# power_stage.net
KiCad netlist of a schematic drawn in Altium Designer
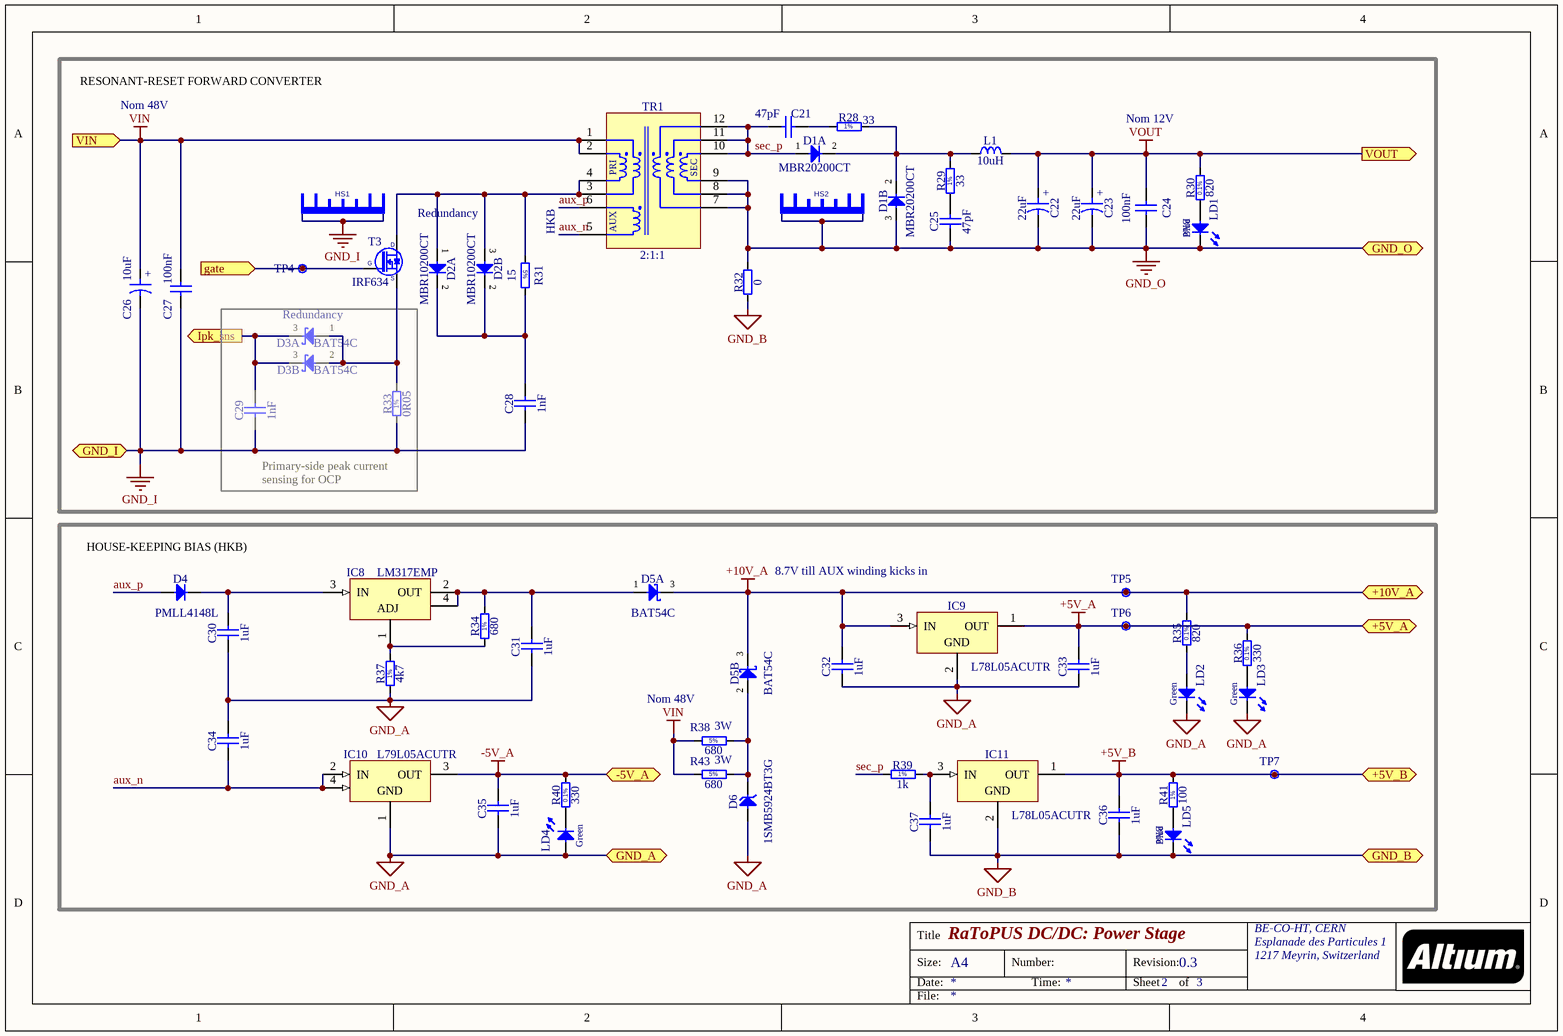
[diagram p0: power_stage.schdoc]

(export (version "E")
  (design (tool "Eeschema 10.0.6"))
  (components
    (comp (ref "C21")
      (value "47pF")
      (footprint "CAPC2012X88N")
      (description "Non-polarised capacitor")
      (fields
        (field (name "PART NUMBER") "CC0805_47PF_50V_5%_C0G_KEMET_C0805C470J5GACAUTO")
        (field (name "VOLTAGE") "50V")
        (field (name "AUTHOR") "CERN DEM JLC")
      )
      (libsource (lib "Capacitors") (part "Capacitor - non polarized"))
    )
    (comp (ref "C22")
      (value "22uF")
      (footprint "CAPPR200-500X700")
      (description "Polarised capacitor")
      (fields
        (field (name "PART NUMBER") "CAER_22UF_25V_20%_200-500X700")
        (field (name "VOLTAGE") "25V")
        (field (name "AUTHOR") "CERN DEM JLC")
      )
      (libsource (lib "Capacitors") (part "Capacitor - polarized"))
    )
    (comp (ref "C23")
      (value "22uF")
      (footprint "CAPPR200-500X700")
      (description "Polarised capacitor")
      (fields
        (field (name "PART NUMBER") "CAER_22UF_25V_20%_200-500X700")
        (field (name "VOLTAGE") "25V")
        (field (name "AUTHOR") "CERN DEM JLC")
      )
      (libsource (lib "Capacitors") (part "Capacitor - polarized"))
    )
    (comp (ref "C24")
      (value "100nF")
      (footprint "CAPC2012X135N")
      (description "Non-polarised capacitor")
      (fields
        (field (name "PART NUMBER") "CC0805_100NF_50V_10%_X7R")
        (field (name "VOLTAGE") "50V")
        (field (name "AUTHOR") "CERN DEM JLC")
      )
      (libsource (lib "Capacitors") (part "Capacitor - non polarized"))
    )
    (comp (ref "C25")
      (value "47pF")
      (footprint "CAPC2012X88N")
      (description "Non-polarised capacitor")
      (fields
        (field (name "PART NUMBER") "CC0805_47PF_50V_5%_C0G_KEMET_C0805C470J5GACAUTO")
        (field (name "VOLTAGE") "50V")
        (field (name "AUTHOR") "CERN DEM JLC")
      )
      (libsource (lib "Capacitors") (part "Capacitor - non polarized"))
    )
    (comp (ref "C26")
      (value "10uF")
      (footprint "CAPPR200-500X1100")
      (description "Polarised capacitor")
      (fields
        (field (name "PART NUMBER") "CAER_10UF_63V_20%_PANASONIC_ECA1JM100")
        (field (name "VOLTAGE") "63V")
        (field (name "AUTHOR") "CERN DEM JLC")
      )
      (libsource (lib "Capacitors") (part "Capacitor - polarized"))
    )
    (comp (ref "C27")
      (value "100nF")
      (footprint "CAPC2012X135N")
      (description "Non-polarised capacitor")
      (fields
        (field (name "PART NUMBER") "CC0805_100NF_50V_10%_X7R")
        (field (name "VOLTAGE") "50V")
        (field (name "AUTHOR") "CERN DEM JLC")
      )
      (libsource (lib "Capacitors") (part "Capacitor - non polarized"))
    )
    (comp (ref "C28")
      (value "1nF")
      (footprint "CAPR500-300X720X750")
      (description "Non-polarised capacitor")
      (fields
        (field (name "PART NUMBER") "CPPR_1NF_400V_10%_WIMA_MKP2")
        (field (name "VOLTAGE") "400VDC")
        (field (name "AUTHOR") "CERN DEM MR")
      )
      (libsource (lib "Capacitors") (part "Capacitor - non polarized"))
    )
    (comp (ref "C29")
      (value "1nF")
      (footprint "CAPC2013X100N")
      (description "Non-polarised capacitor")
      (fields
        (field (name "PART NUMBER") "CC0805_1NF_25V_1%_C0G")
        (field (name "VOLTAGE") "25V")
        (field (name "AUTHOR") "CERN DEM JLC")
      )
      (libsource (lib "Capacitors") (part "Capacitor - non polarized"))
    )
    (comp (ref "C30")
      (value "1uF")
      (footprint "CAPC3216X140N")
      (description "Non-polarised capacitor")
      (fields
        (field (name "PART NUMBER") "CC1206_1UF_50V_10%_X7R")
        (field (name "VOLTAGE") "50V")
        (field (name "AUTHOR") "CERN DEM JLC")
      )
      (libsource (lib "Capacitors") (part "Capacitor - non polarized"))
    )
    (comp (ref "C31")
      (value "1uF")
      (footprint "CAPC3216X140N")
      (description "Non-polarised capacitor")
      (fields
        (field (name "PART NUMBER") "CC1206_1UF_50V_10%_X7R")
        (field (name "VOLTAGE") "50V")
        (field (name "AUTHOR") "CERN DEM JLC")
      )
      (libsource (lib "Capacitors") (part "Capacitor - non polarized"))
    )
    (comp (ref "C32")
      (value "1uF")
      (footprint "CAPC3216X140N")
      (description "Non-polarised capacitor")
      (fields
        (field (name "PART NUMBER") "CC1206_1UF_50V_10%_X7R")
        (field (name "VOLTAGE") "50V")
        (field (name "AUTHOR") "CERN DEM JLC")
      )
      (libsource (lib "Capacitors") (part "Capacitor - non polarized"))
    )
    (comp (ref "C33")
      (value "1uF")
      (footprint "CAPC3216X140N")
      (description "Non-polarised capacitor")
      (fields
        (field (name "PART NUMBER") "CC1206_1UF_50V_10%_X7R")
        (field (name "VOLTAGE") "50V")
        (field (name "AUTHOR") "CERN DEM JLC")
      )
      (libsource (lib "Capacitors") (part "Capacitor - non polarized"))
    )
    (comp (ref "C34")
      (value "1uF")
      (footprint "CAPC3216X140N")
      (description "Non-polarised capacitor")
      (fields
        (field (name "PART NUMBER") "CC1206_1UF_50V_10%_X7R")
        (field (name "VOLTAGE") "50V")
        (field (name "AUTHOR") "CERN DEM JLC")
      )
      (libsource (lib "Capacitors") (part "Capacitor - non polarized"))
    )
    (comp (ref "C35")
      (value "1uF")
      (footprint "CAPC3216X140N")
      (description "Non-polarised capacitor")
      (fields
        (field (name "PART NUMBER") "CC1206_1UF_50V_10%_X7R")
        (field (name "VOLTAGE") "50V")
        (field (name "AUTHOR") "CERN DEM JLC")
      )
      (libsource (lib "Capacitors") (part "Capacitor - non polarized"))
    )
    (comp (ref "C36")
      (value "1uF")
      (footprint "CAPC3216X140N")
      (description "Non-polarised capacitor")
      (fields
        (field (name "PART NUMBER") "CC1206_1UF_50V_10%_X7R")
        (field (name "VOLTAGE") "50V")
        (field (name "AUTHOR") "CERN DEM JLC")
      )
      (libsource (lib "Capacitors") (part "Capacitor - non polarized"))
    )
    (comp (ref "C37")
      (value "1uF")
      (footprint "CAPC3216X140N")
      (description "Non-polarised capacitor")
      (fields
        (field (name "PART NUMBER") "CC1206_1UF_50V_10%_X7R")
        (field (name "VOLTAGE") "50V")
        (field (name "AUTHOR") "CERN DEM JLC")
      )
      (libsource (lib "Capacitors") (part "Capacitor - non polarized"))
    )
    (comp (ref "D1")
      (value "MBR20200CT")
      (footprint "TO-220-V")
      (description "Dual Common Cathode Diodes")
      (fields
        (field (name "PART NUMBER") "MBR20200CT_v")
        (field (name "VOLTAGE") "200V")
        (field (name "AUTHOR") "CERN DEM JLC")
      )
      (libsource (lib "ICs And Semiconductors") (part "Diode x2 A1C2_A3C2"))
    )
    (comp (ref "D2")
      (value "MBR10200CT")
      (footprint "TO-220-V")
      (description "Dual Common Cathode Diodes")
      (fields
        (field (name "PART NUMBER") "MBR10200CT_v")
        (field (name "VOLTAGE") "200V")
        (field (name "AUTHOR") "CERN DEM JLC")
      )
      (libsource (lib "ICs And Semiconductors") (part "Diode x2 A1C2_A3C2"))
    )
    (comp (ref "D3")
      (value "BAT54C")
      (footprint "SOT95P240X130-3N")
      (description "Dual Common Cathode Schottky Diodes")
      (fields
        (field (name "VOLTAGE") "30V")
        (field (name "POWER") "200mA")
        (field (name "AUTHOR") "CERN DEM JLC")
      )
      (libsource (lib "ICs And Semiconductors") (part "Diode Schottky x2 A1C3_A2C3"))
    )
    (comp (ref "D4")
      (value "PMLL4148L")
      (footprint "DIOMELF3515N")
      (description "Diode")
      (fields
        (field (name "VOLTAGE") "75V")
        (field (name "POWER") "200mA")
        (field (name "AUTHOR") "CERN DEM JLC")
      )
      (libsource (lib "ICs And Semiconductors") (part "Diode"))
    )
    (comp (ref "D5")
      (value "BAT54C")
      (footprint "SOT95P240X130-3N")
      (description "Dual Common Cathode Schottky Diodes")
      (fields
        (field (name "VOLTAGE") "30V")
        (field (name "POWER") "200mA")
        (field (name "AUTHOR") "CERN DEM JLC")
      )
      (libsource (lib "ICs And Semiconductors") (part "Diode Schottky x2 A1C3_A2C3"))
    )
    (comp (ref "D6")
      (value "1SMB5924BT3G")
      (footprint "DIOM5436X244N")
      (description "Zener Diode")
      (fields
        (field (name "VOLTAGE") "9.1V")
        (field (name "POWER") "3W")
        (field (name "AUTHOR") "CERN DEM BC")
      )
      (libsource (lib "ICs And Semiconductors") (part "Diode Zener"))
    )
    (comp (ref "HS1")
      (value "Heat Sink 2 Pads")
      (footprint "HSINK_AAVID-THERMALLOY_530002B02500G_v")
      (description "Heat Sink With 2 pads")
      (fields
        (field (name "PART NUMBER") "HSINK_AAVID-THERMALLOY_530002B02500G_v")
        (field (name "MANUFACTURER") "AAVID THERMALLOY")
        (field (name "AUTHOR") "CERN DEM JLC")
      )
      (libsource (lib "Eletro-mechanical") (part "Heat Sink 2 Pads"))
    )
    (comp (ref "HS2")
      (value "Heat Sink 2 Pads")
      (footprint "HSINK_AAVID-THERMALLOY_530002B02500G_v")
      (description "Heat Sink With 2 pads")
      (fields
        (field (name "PART NUMBER") "HSINK_AAVID-THERMALLOY_530002B02500G_v")
        (field (name "MANUFACTURER") "AAVID THERMALLOY")
        (field (name "AUTHOR") "CERN DEM JLC")
      )
      (libsource (lib "Eletro-mechanical") (part "Heat Sink 2 Pads"))
    )
    (comp (ref "IC8")
      (value "LM317EMP")
      (footprint "SOT230P700X180-4N")
      (description "3-Terminal Regulator 1=Adj 2=OUT 3=IN 4=OUT")
      (fields (field (name "MANUFACTURER") "TEXAS INSTRUMENTS") (field (name "AUTHOR") "CERN DEM JLC"))
      (libsource (lib "ICs And Semiconductors") (part "REG3+1 1ADJ-2OUT-3IN+4OUT"))
    )
    (comp (ref "IC9")
      (value "L78L05ACUTR")
      (footprint "SOT89")
      (description "3-Terminal Regulator 1=OUT 2=GND 3=IN")
      (fields (field (name "MANUFACTURER") "ST MICROELECTRONICS") (field (name "AUTHOR") "CERN DEM JLC"))
      (libsource (lib "ICs And Semiconductors") (part "REG3 1OUT-2GND-3IN"))
    )
    (comp (ref "IC10")
      (value "L79L05ACUTR")
      (footprint "SOT89")
      (description "3-Terminal Regulator 1=GND 2=IN 3=OUT 4=IN")
      (fields (field (name "MANUFACTURER") "ST MICROELECTRONICS") (field (name "AUTHOR") "CERN DEM JLC"))
      (libsource (lib "ICs And Semiconductors") (part "REG3+1 1GND-2IN-3OUT+4IN"))
    )
    (comp (ref "IC11")
      (value "L78L05ACUTR")
      (footprint "SOT89")
      (description "3-Terminal Regulator 1=OUT 2=GND 3=IN")
      (fields (field (name "MANUFACTURER") "ST MICROELECTRONICS") (field (name "AUTHOR") "CERN DEM JLC"))
      (libsource (lib "ICs And Semiconductors") (part "REG3 1OUT-2GND-3IN"))
    )
    (comp (ref "L1")
      (value "10uH")
      (footprint "IND_BOURNS_SRP1038A")
      (description "Inductor")
      (fields
        (field (name "PART NUMBER") "IND_10UH_20%_BOURNS_SRP1038A")
        (field (name "POWER") "7.5A")
        (field (name "AUTHOR") "CERN DEM MR")
      )
      (libsource (lib "Inductors & Transformers") (part "Inductor"))
    )
    (comp (ref "LD1")
      (value "Blue")
      (footprint "LED_KINGBRIGHT_KPH-1608QBC-D")
      (description "LED Blue 1C 2A")
      (fields
        (field (name "PART NUMBER") "LED_KINGBRIGHT_KPH-1608QBC-D")
        (field (name "MANUFACTURER") "KINGBRIGHT")
        (field (name "AUTHOR") "CERN DEM JLC")
      )
      (libsource (lib "ICs And Semiconductors") (part "LED Blue 1C 2A"))
    )
    (comp (ref "LD2")
      (value "Green")
      (footprint "LED_KINGBRIGHT_KPH-1608CGCK")
      (description "LED Green 1C 2A")
      (fields
        (field (name "PART NUMBER") "LED_KINGBRIGHT_KPH-1608CGCK")
        (field (name "MANUFACTURER") "KINGBRIGHT")
        (field (name "AUTHOR") "CERN DEM JLC")
      )
      (libsource (lib "ICs And Semiconductors") (part "LED Green 1C 2A"))
    )
    (comp (ref "LD3")
      (value "Green")
      (footprint "LED_KINGBRIGHT_KPH-1608CGCK")
      (description "LED Green 1C 2A")
      (fields
        (field (name "PART NUMBER") "LED_KINGBRIGHT_KPH-1608CGCK")
        (field (name "MANUFACTURER") "KINGBRIGHT")
        (field (name "AUTHOR") "CERN DEM JLC")
      )
      (libsource (lib "ICs And Semiconductors") (part "LED Green 1C 2A"))
    )
    (comp (ref "LD4")
      (value "Green")
      (footprint "LED_KINGBRIGHT_KPH-1608CGCK")
      (description "LED Green 1C 2A")
      (fields
        (field (name "PART NUMBER") "LED_KINGBRIGHT_KPH-1608CGCK")
        (field (name "MANUFACTURER") "KINGBRIGHT")
        (field (name "AUTHOR") "CERN DEM JLC")
      )
      (libsource (lib "ICs And Semiconductors") (part "LED Green 1C 2A"))
    )
    (comp (ref "LD5")
      (value "Blue")
      (footprint "LED_KINGBRIGHT_KPH-1608QBC-D")
      (description "LED Blue 1C 2A")
      (fields
        (field (name "PART NUMBER") "LED_KINGBRIGHT_KPH-1608QBC-D")
        (field (name "MANUFACTURER") "KINGBRIGHT")
        (field (name "AUTHOR") "CERN DEM JLC")
      )
      (libsource (lib "ICs And Semiconductors") (part "LED Blue 1C 2A"))
    )
    (comp (ref "R28")
      (value "33")
      (footprint "RESC2012X60N")
      (description "Resistor - 1%")
      (fields
        (field (name "PART NUMBER") "R0805_33R_1%_0.125W_100PPM")
        (field (name "POWER") "0.125W")
        (field (name "AUTHOR") "CERN DEM JLC")
      )
      (libsource (lib "Resistors") (part "Resistor - 1%"))
    )
    (comp (ref "R29")
      (value "33")
      (footprint "RESC2012X60N")
      (description "Resistor - 1%")
      (fields
        (field (name "PART NUMBER") "R0805_33R_1%_0.125W_100PPM")
        (field (name "POWER") "0.125W")
        (field (name "AUTHOR") "CERN DEM JLC")
      )
      (libsource (lib "Resistors") (part "Resistor - 1%"))
    )
    (comp (ref "R30")
      (value "820")
      (footprint "RESC2012X60N")
      (description "Resistor - 0.1%")
      (fields
        (field (name "PART NUMBER") "R0805_820R_0.1%_0.125W_10PPM")
        (field (name "POWER") "0.125W")
        (field (name "AUTHOR") "CERN DEM JLC")
      )
      (libsource (lib "Resistors") (part "Resistor - 0.1%"))
    )
    (comp (ref "R31")
      (value "15")
      (footprint "RES1270-650X250")
      (description "Resistor - 5%")
      (fields
        (field (name "PART NUMBER") "RMF_15R_5%_1W_250PPM_1270-650X250")
        (field (name "POWER") "1W")
        (field (name "AUTHOR") "CERN DEM JLC")
      )
      (libsource (lib "Resistors") (part "Resistor - 5%"))
    )
    (comp (ref "R32")
      (value "0")
      (footprint "RESC2012X60N")
      (description "Resistor")
      (fields
        (field (name "PART NUMBER") "R0805_0R_JUMPER")
        (field (name "MANUFACTURER") "GENERIC")
        (field (name "AUTHOR") "CERN DEM JLC")
      )
      (libsource (lib "Resistors") (part "Resistor"))
    )
    (comp (ref "R33")
      (value "0R05")
      (footprint "RESC3216X80N")
      (description "Resistor - 1%")
      (fields
        (field (name "PART NUMBER") "R1206_0R05_1%_1W_150PPM")
        (field (name "POWER") "1W")
        (field (name "AUTHOR") "CERN DEM JLC")
      )
      (libsource (lib "Resistors") (part "Resistor - 1%"))
    )
    (comp (ref "R34")
      (value "680")
      (footprint "RESC2012X60N")
      (description "Resistor - 1%")
      (fields
        (field (name "PART NUMBER") "R0805_680R_1%_0.125W_100PPM")
        (field (name "POWER") "0.125W")
        (field (name "AUTHOR") "CERN DEM JLC")
      )
      (libsource (lib "Resistors") (part "Resistor - 1%"))
    )
    (comp (ref "R35")
      (value "820")
      (footprint "RESC2012X60N")
      (description "Resistor - 0.1%")
      (fields
        (field (name "PART NUMBER") "R0805_820R_0.1%_0.125W_10PPM")
        (field (name "POWER") "0.125W")
        (field (name "AUTHOR") "CERN DEM JLC")
      )
      (libsource (lib "Resistors") (part "Resistor - 0.1%"))
    )
    (comp (ref "R36")
      (value "330")
      (footprint "RESC2012X60N")
      (description "Resistor - 0.1%")
      (fields
        (field (name "PART NUMBER") "R0805_330R_0.1%_0.1W_25PPM")
        (field (name "POWER") "0.1W")
        (field (name "AUTHOR") "CERN DEM JLC")
      )
      (libsource (lib "Resistors") (part "Resistor - 0.1%"))
    )
    (comp (ref "R37")
      (value "4k7")
      (footprint "RESC2012X60N")
      (description "Resistor - 1%")
      (fields
        (field (name "PART NUMBER") "R0805_4K7_1%_0.125W_100PPM")
        (field (name "POWER") "0.125W")
        (field (name "AUTHOR") "CERN DEM JLC")
      )
      (libsource (lib "Resistors") (part "Resistor - 1%"))
    )
    (comp (ref "R38")
      (value "680")
      (footprint "RES2286-1670X520")
      (description "Resistor - 5%")
      (fields
        (field (name "PART NUMBER") "RMF_680R_5%_3W_250PPM_2286-1670X520")
        (field (name "POWER") "3W")
        (field (name "AUTHOR") "CERN DEM JLC")
      )
      (libsource (lib "Resistors") (part "Resistor - 5%"))
    )
    (comp (ref "R39")
      (value "1k")
      (footprint "RESC2012X60N")
      (description "Resistor - 1%")
      (fields
        (field (name "PART NUMBER") "R0805_1K_1%_0.125W_100PPM")
        (field (name "POWER") "0.125W")
        (field (name "AUTHOR") "CERN DEM JLC")
      )
      (libsource (lib "Resistors") (part "Resistor - 1%"))
    )
    (comp (ref "R40")
      (value "330")
      (footprint "RESC2012X60N")
      (description "Resistor - 0.1%")
      (fields
        (field (name "PART NUMBER") "R0805_330R_0.1%_0.1W_25PPM")
        (field (name "POWER") "0.1W")
        (field (name "AUTHOR") "CERN DEM JLC")
      )
      (libsource (lib "Resistors") (part "Resistor - 0.1%"))
    )
    (comp (ref "R41")
      (value "100")
      (footprint "RESC2012X60N")
      (description "Resistor - 1%")
      (fields
        (field (name "PART NUMBER") "R0805_100R_1%_0.125W_100PPM")
        (field (name "POWER") "0.125W")
        (field (name "AUTHOR") "CERN DEM JLC")
      )
      (libsource (lib "Resistors") (part "Resistor - 1%"))
    )
    (comp (ref "R43")
      (value "680")
      (footprint "RES2286-1670X520")
      (description "Resistor - 5%")
      (fields
        (field (name "PART NUMBER") "RMF_680R_5%_3W_250PPM_2286-1670X520")
        (field (name "POWER") "3W")
        (field (name "AUTHOR") "CERN DEM JLC")
      )
      (libsource (lib "Resistors") (part "Resistor - 5%"))
    )
    (comp (ref "T3")
      (value "IRF634")
      (footprint "TO-220-V")
      (description "N-CHANNEL MOSFET WITH DIODE")
      (fields
        (field (name "PART NUMBER") "IRF634_v")
        (field (name "MANUFACTURER") "VISHAY SILICONIX")
        (field (name "AUTHOR") "CERN DEM JLC")
      )
      (libsource (lib "ICs And Semiconductors") (part "N-MOSFET-D 1G 2D 3S"))
    )
    (comp (ref "TP4")
      (value "Test Point")
      (footprint "VERO_20-2136")
      (fields
        (field (name "PART NUMBER") "VERO_20-2136")
        (field (name "MANUFACTURER") "VERO TECHNOLOGIES")
        (field (name "MANUFACTURER PART NUMBER") "20-2136")
        (field (name "AUTHOR") "CERN DEM JLC")
      )
      (libsource (lib "Connectors") (part "Test Point"))
    )
    (comp (ref "TP5")
      (value "Test Point")
      (footprint "VERO_20-2136")
      (fields
        (field (name "PART NUMBER") "VERO_20-2136")
        (field (name "MANUFACTURER") "VERO TECHNOLOGIES")
        (field (name "MANUFACTURER PART NUMBER") "20-2136")
        (field (name "AUTHOR") "CERN DEM JLC")
      )
      (libsource (lib "Connectors") (part "Test Point"))
    )
    (comp (ref "TP6")
      (value "Test Point")
      (footprint "VERO_20-2136")
      (fields
        (field (name "PART NUMBER") "VERO_20-2136")
        (field (name "MANUFACTURER") "VERO TECHNOLOGIES")
        (field (name "MANUFACTURER PART NUMBER") "20-2136")
        (field (name "AUTHOR") "CERN DEM JLC")
      )
      (libsource (lib "Connectors") (part "Test Point"))
    )
    (comp (ref "TP7")
      (value "Test Point")
      (footprint "VERO_20-2136")
      (fields
        (field (name "PART NUMBER") "VERO_20-2136")
        (field (name "MANUFACTURER") "VERO TECHNOLOGIES")
        (field (name "MANUFACTURER PART NUMBER") "20-2136")
        (field (name "AUTHOR") "CERN DEM JLC")
      )
      (libsource (lib "Connectors") (part "Test Point"))
    )
    (comp (ref "TR1")
      (value "2:1:1")
      (footprint "XFMR_COILCRAFT_POE600F")
      (description "60W PoE Transformer")
      (fields
        (field (name "PART NUMBER") "XFMR_COILCRAFT_POE600F-12L")
        (field (name "MANUFACTURER") "COILCRAFT")
        (field (name "AUTHOR") "CERN DEM JLC")
      )
      (libsource (lib "Inductors & Transformers") (part "XFMR_COILCRAFT_POE600F"))
    )
  )
  (nets
    (net (code "1") (name "+5V_A") (class "Default")
      (node (ref "C33") (pin "2") (pinfunction "2_2") (pintype "passive"))
      (node (ref "IC9") (pin "1") (pinfunction "OUT_1") (pintype "power_in"))
      (node (ref "R36") (pin "2") (pinfunction "2_2") (pintype "passive"))
      (node (ref "TP6") (pin "1") (pinfunction "1_1") (pintype "bidirectional"))
    )
    (net (code "2") (name "+5V_B") (class "Default")
      (node (ref "C36") (pin "2") (pinfunction "2_2") (pintype "passive"))
      (node (ref "IC11") (pin "1") (pinfunction "OUT_1") (pintype "power_in"))
      (node (ref "R41") (pin "2") (pinfunction "2_2") (pintype "passive"))
      (node (ref "TP7") (pin "1") (pinfunction "1_1") (pintype "bidirectional"))
    )
    (net (code "3") (name "+10V_A") (class "Default")
      (node (ref "C32") (pin "2") (pinfunction "2_2") (pintype "passive"))
      (node (ref "D5") (pin "3") (pinfunction "COMC_3") (pintype "passive"))
      (node (ref "IC9") (pin "3") (pinfunction "IN_3") (pintype "input"))
      (node (ref "R35") (pin "2") (pinfunction "2_2") (pintype "passive"))
      (node (ref "TP5") (pin "1") (pinfunction "1_1") (pintype "bidirectional"))
    )
    (net (code "4") (name "-5V_A") (class "Default")
      (node (ref "C35") (pin "2") (pinfunction "2_2") (pintype "passive"))
      (node (ref "IC10") (pin "3") (pinfunction "OUT_3") (pintype "power_in"))
      (node (ref "R40") (pin "2") (pinfunction "2_2") (pintype "passive"))
    )
    (net (code "5") (name "/Ipk_sns") (class "Default")
      (node (ref "C29") (pin "2") (pinfunction "2_2") (pintype "passive"))
      (node (ref "D3") (pin "3") (pinfunction "COMC_3") (pintype "passive"))
    )
    (net (code "6") (name "/aux_n") (class "Default")
      (node (ref "C34") (pin "1") (pinfunction "1_1") (pintype "passive"))
      (node (ref "IC10") (pin "2") (pinfunction "IN_2") (pintype "input"))
      (node (ref "IC10") (pin "4") (pinfunction "IN_4") (pintype "input"))
      (node (ref "TR1") (pin "5") (pinfunction "AUX_5") (pintype "passive"))
    )
    (net (code "7") (name "/aux_p") (class "Default")
      (node (ref "D4") (pin "2") (pinfunction "A_2") (pintype "passive"))
      (node (ref "TR1") (pin "6") (pinfunction "AUX_6") (pintype "passive"))
    )
    (net (code "8") (name "/gate") (class "Default")
      (node (ref "T3") (pin "1") (pinfunction "G_1") (pintype "passive"))
      (node (ref "TP4") (pin "1") (pinfunction "1_1") (pintype "bidirectional"))
    )
    (net (code "9") (name "/sec_p") (class "Default")
      (node (ref "C21") (pin "1") (pinfunction "1_1") (pintype "passive"))
      (node (ref "D1") (pin "1") (pinfunction "A_1") (pintype "passive"))
      (node (ref "R39") (pin "1") (pinfunction "1_1") (pintype "passive"))
      (node (ref "TR1") (pin "10") (pinfunction "SEC_10") (pintype "passive"))
      (node (ref "TR1") (pin "11") (pinfunction "SEC_11") (pintype "passive"))
      (node (ref "TR1") (pin "12") (pinfunction "SEC_12") (pintype "passive"))
    )
    (net (code "10") (name "GND_A") (class "Default")
      (node (ref "C30") (pin "1") (pinfunction "1_1") (pintype "passive"))
      (node (ref "C31") (pin "1") (pinfunction "1_1") (pintype "passive"))
      (node (ref "C32") (pin "1") (pinfunction "1_1") (pintype "passive"))
      (node (ref "C33") (pin "1") (pinfunction "1_1") (pintype "passive"))
      (node (ref "C34") (pin "2") (pinfunction "2_2") (pintype "passive"))
      (node (ref "C35") (pin "1") (pinfunction "1_1") (pintype "passive"))
      (node (ref "D6") (pin "2") (pinfunction "A_2") (pintype "passive"))
      (node (ref "IC10") (pin "1") (pinfunction "GND_1") (pintype "power_in"))
      (node (ref "IC9") (pin "2") (pinfunction "GND_2") (pintype "power_in"))
      (node (ref "LD2") (pin "1") (pinfunction "C_1") (pintype "passive"))
      (node (ref "LD3") (pin "1") (pinfunction "C_1") (pintype "passive"))
      (node (ref "LD4") (pin "2") (pinfunction "A_2") (pintype "passive"))
      (node (ref "R37") (pin "1") (pinfunction "1_1") (pintype "passive"))
    )
    (net (code "11") (name "GND_B") (class "Default")
      (node (ref "C36") (pin "1") (pinfunction "1_1") (pintype "passive"))
      (node (ref "C37") (pin "1") (pinfunction "1_1") (pintype "passive"))
      (node (ref "IC11") (pin "2") (pinfunction "GND_2") (pintype "power_in"))
      (node (ref "LD5") (pin "1") (pinfunction "C_1") (pintype "passive"))
      (node (ref "R32") (pin "1") (pinfunction "1_1") (pintype "passive"))
    )
    (net (code "12") (name "GND_I") (class "Default")
      (node (ref "C26") (pin "2") (pinfunction "2_2") (pintype "passive"))
      (node (ref "C27") (pin "1") (pinfunction "1_1") (pintype "passive"))
      (node (ref "C28") (pin "1") (pinfunction "1_1") (pintype "passive"))
      (node (ref "C29") (pin "1") (pinfunction "1_1") (pintype "passive"))
      (node (ref "HS1") (pin "1") (pinfunction "1_1") (pintype "passive"))
      (node (ref "HS1") (pin "2") (pinfunction "2_2") (pintype "passive"))
      (node (ref "R33") (pin "1") (pinfunction "1_1") (pintype "passive"))
    )
    (net (code "13") (name "GND_O") (class "Default")
      (node (ref "C22") (pin "2") (pinfunction "2_2") (pintype "passive"))
      (node (ref "C23") (pin "2") (pinfunction "2_2") (pintype "passive"))
      (node (ref "C24") (pin "1") (pinfunction "1_1") (pintype "passive"))
      (node (ref "C25") (pin "1") (pinfunction "1_1") (pintype "passive"))
      (node (ref "D1") (pin "3") (pinfunction "A_3") (pintype "passive"))
      (node (ref "HS2") (pin "1") (pinfunction "1_1") (pintype "passive"))
      (node (ref "HS2") (pin "2") (pinfunction "2_2") (pintype "passive"))
      (node (ref "LD1") (pin "1") (pinfunction "C_1") (pintype "passive"))
      (node (ref "R32") (pin "2") (pinfunction "2_2") (pintype "passive"))
      (node (ref "TR1") (pin "7") (pinfunction "SEC_7") (pintype "passive"))
      (node (ref "TR1") (pin "8") (pinfunction "SEC_8") (pintype "passive"))
      (node (ref "TR1") (pin "9") (pinfunction "SEC_9") (pintype "passive"))
    )
    (net (code "14") (name "Net-(C21-Pad2)") (class "Default")
      (node (ref "C21") (pin "2") (pinfunction "2_2") (pintype "passive"))
      (node (ref "R28") (pin "1") (pinfunction "1_1") (pintype "passive"))
    )
    (net (code "15") (name "Net-(C25-Pad2)") (class "Default")
      (node (ref "C25") (pin "2") (pinfunction "2_2") (pintype "passive"))
      (node (ref "R29") (pin "1") (pinfunction "1_1") (pintype "passive"))
    )
    (net (code "16") (name "Net-(D1A-COMC)") (class "Default")
      (node (ref "D1") (pin "2") (pinfunction "COMC_2") (pintype "passive"))
      (node (ref "L1") (pin "1") (pinfunction "1_1") (pintype "passive"))
      (node (ref "R28") (pin "2") (pinfunction "2_2") (pintype "passive"))
      (node (ref "R29") (pin "2") (pinfunction "2_2") (pintype "passive"))
    )
    (net (code "17") (name "Net-(D2A-A)") (class "Default")
      (node (ref "D2") (pin "1") (pinfunction "A_1") (pintype "passive"))
      (node (ref "D2") (pin "3") (pinfunction "A_3") (pintype "passive"))
      (node (ref "R31") (pin "1") (pinfunction "1_1") (pintype "passive"))
      (node (ref "T3") (pin "2") (pinfunction "D_2") (pintype "passive"))
      (node (ref "TR1") (pin "3") (pinfunction "PRI_3") (pintype "passive"))
      (node (ref "TR1") (pin "4") (pinfunction "PRI_4") (pintype "passive"))
    )
    (net (code "18") (name "Net-(D2A-COMC)") (class "Default")
      (node (ref "C28") (pin "2") (pinfunction "2_2") (pintype "passive"))
      (node (ref "D2") (pin "2") (pinfunction "COMC_2") (pintype "passive"))
      (node (ref "R31") (pin "2") (pinfunction "2_2") (pintype "passive"))
    )
    (net (code "19") (name "Net-(D3A-A)") (class "Default")
      (node (ref "D3") (pin "1") (pinfunction "A_1") (pintype "passive"))
      (node (ref "D3") (pin "2") (pinfunction "A_2") (pintype "passive"))
      (node (ref "R33") (pin "2") (pinfunction "2_2") (pintype "passive"))
      (node (ref "T3") (pin "3") (pinfunction "S_3") (pintype "passive"))
    )
    (net (code "20") (name "Net-(D4-C)") (class "Default")
      (node (ref "C30") (pin "2") (pinfunction "2_2") (pintype "passive"))
      (node (ref "D4") (pin "1") (pinfunction "C_1") (pintype "passive"))
      (node (ref "IC8") (pin "3") (pinfunction "IN_3") (pintype "input"))
    )
    (net (code "21") (name "Net-(D5A-A)") (class "Default")
      (node (ref "C31") (pin "2") (pinfunction "2_2") (pintype "passive"))
      (node (ref "D5") (pin "1") (pinfunction "A_1") (pintype "passive"))
      (node (ref "IC8") (pin "2") (pinfunction "OUT_2") (pintype "power_in"))
      (node (ref "IC8") (pin "4") (pinfunction "OUT_4") (pintype "power_in"))
      (node (ref "R34") (pin "2") (pinfunction "2_2") (pintype "passive"))
    )
    (net (code "22") (name "Net-(D5B-A)") (class "Default")
      (node (ref "D5") (pin "2") (pinfunction "A_2") (pintype "passive"))
      (node (ref "D6") (pin "1") (pinfunction "C_1") (pintype "passive"))
      (node (ref "R38") (pin "2") (pinfunction "2_2") (pintype "passive"))
      (node (ref "R43") (pin "2") (pinfunction "2_2") (pintype "passive"))
    )
    (net (code "23") (name "Net-(IC8-ADJ)") (class "Default")
      (node (ref "IC8") (pin "1") (pinfunction "ADJ_1") (pintype "power_in"))
      (node (ref "R34") (pin "1") (pinfunction "1_1") (pintype "passive"))
      (node (ref "R37") (pin "2") (pinfunction "2_2") (pintype "passive"))
    )
    (net (code "24") (name "Net-(IC11-IN)") (class "Default")
      (node (ref "C37") (pin "2") (pinfunction "2_2") (pintype "passive"))
      (node (ref "IC11") (pin "3") (pinfunction "IN_3") (pintype "input"))
      (node (ref "R39") (pin "2") (pinfunction "2_2") (pintype "passive"))
    )
    (net (code "25") (name "Net-(LD1-A)") (class "Default")
      (node (ref "LD1") (pin "2") (pinfunction "A_2") (pintype "passive"))
      (node (ref "R30") (pin "1") (pinfunction "1_1") (pintype "passive"))
    )
    (net (code "26") (name "Net-(LD2-A)") (class "Default")
      (node (ref "LD2") (pin "2") (pinfunction "A_2") (pintype "passive"))
      (node (ref "R35") (pin "1") (pinfunction "1_1") (pintype "passive"))
    )
    (net (code "27") (name "Net-(LD3-A)") (class "Default")
      (node (ref "LD3") (pin "2") (pinfunction "A_2") (pintype "passive"))
      (node (ref "R36") (pin "1") (pinfunction "1_1") (pintype "passive"))
    )
    (net (code "28") (name "Net-(LD4-C)") (class "Default")
      (node (ref "LD4") (pin "1") (pinfunction "C_1") (pintype "passive"))
      (node (ref "R40") (pin "1") (pinfunction "1_1") (pintype "passive"))
    )
    (net (code "29") (name "Net-(LD5-A)") (class "Default")
      (node (ref "LD5") (pin "2") (pinfunction "A_2") (pintype "passive"))
      (node (ref "R41") (pin "1") (pinfunction "1_1") (pintype "passive"))
    )
    (net (code "30") (name "VIN") (class "Default")
      (node (ref "C26") (pin "1") (pinfunction "1_1") (pintype "passive"))
      (node (ref "C27") (pin "2") (pinfunction "2_2") (pintype "passive"))
      (node (ref "R38") (pin "1") (pinfunction "1_1") (pintype "passive"))
      (node (ref "R43") (pin "1") (pinfunction "1_1") (pintype "passive"))
      (node (ref "TR1") (pin "1") (pinfunction "PRI_1") (pintype "passive"))
      (node (ref "TR1") (pin "2") (pinfunction "PRI_2") (pintype "passive"))
    )
    (net (code "31") (name "VOUT") (class "Default")
      (node (ref "C22") (pin "1") (pinfunction "1_1") (pintype "passive"))
      (node (ref "C23") (pin "1") (pinfunction "1_1") (pintype "passive"))
      (node (ref "C24") (pin "2") (pinfunction "2_2") (pintype "passive"))
      (node (ref "L1") (pin "2") (pinfunction "2_2") (pintype "passive"))
      (node (ref "R30") (pin "2") (pinfunction "2_2") (pintype "passive"))
    )
  )
)
